# untitled.net
KiCad netlist of a schematic drawn in EAGLE
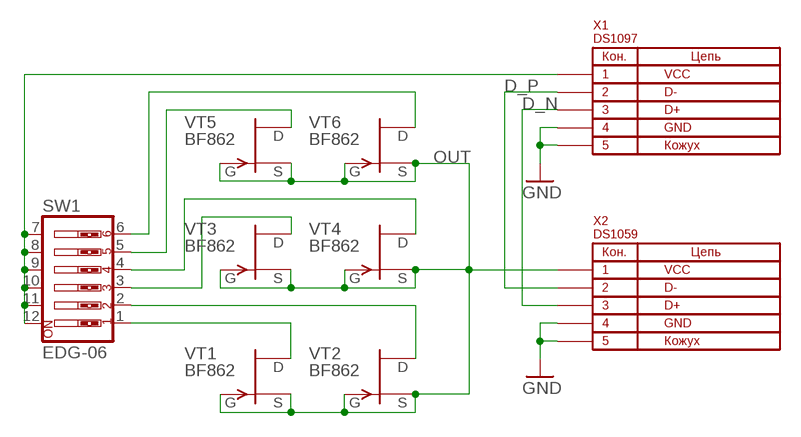
[diagram p0: schematic, sheet 1]

(export (version "E")
  (design (tool "Eeschema 10.0.6"))
  (components
    (comp (ref "SW1")
      (value "EDG-06")
      (footprint "eagle-import:EDG-06")
      (libsource (lib "eagle-import") (part "EDG-06"))
    )
    (comp (ref "VT1")
      (value "BF862")
      (footprint "eagle-import:SOT23")
      (libsource (lib "eagle-import") (part "BF862"))
    )
    (comp (ref "VT2")
      (value "BF862")
      (footprint "eagle-import:SOT23")
      (libsource (lib "eagle-import") (part "BF862"))
    )
    (comp (ref "VT3")
      (value "BF862")
      (footprint "eagle-import:SOT23")
      (libsource (lib "eagle-import") (part "BF862"))
    )
    (comp (ref "VT4")
      (value "BF862")
      (footprint "eagle-import:SOT23")
      (libsource (lib "eagle-import") (part "BF862"))
    )
    (comp (ref "VT5")
      (value "BF862")
      (footprint "eagle-import:SOT23")
      (libsource (lib "eagle-import") (part "BF862"))
    )
    (comp (ref "VT6")
      (value "BF862")
      (footprint "eagle-import:SOT23")
      (libsource (lib "eagle-import") (part "BF862"))
    )
    (comp (ref "X1")
      (value "DS1097")
      (footprint "eagle-import:DS1097")
      (libsource (lib "eagle-import") (part "DS1097"))
    )
    (comp (ref "X2")
      (value "DS1059")
      (footprint "eagle-import:DS1059")
      (libsource (lib "eagle-import") (part "DS1059"))
    )
  )
  (nets
    (net (code "1") (name "/D_N") (class "Default")
      (node (ref "X1") (pin "P$2") (pinfunction "P$3_P$2") (pintype "bidirectional"))
      (node (ref "X2") (pin "P$3") (pinfunction "P$3_P$3") (pintype "bidirectional"))
    )
    (net (code "2") (name "/D_P") (class "Default")
      (node (ref "X1") (pin "P$3") (pinfunction "P$2_P$3") (pintype "bidirectional"))
      (node (ref "X2") (pin "P$2") (pinfunction "P$2_P$2") (pintype "bidirectional"))
    )
    (net (code "3") (name "/OUT") (class "Default")
      (node (ref "VT1") (pin "1") (pinfunction "S_1") (pintype "passive"))
      (node (ref "VT1") (pin "3") (pinfunction "G_3") (pintype "passive"))
      (node (ref "VT2") (pin "1") (pinfunction "S_1") (pintype "passive"))
      (node (ref "VT2") (pin "3") (pinfunction "G_3") (pintype "passive"))
      (node (ref "VT3") (pin "1") (pinfunction "S_1") (pintype "passive"))
      (node (ref "VT3") (pin "3") (pinfunction "G_3") (pintype "passive"))
      (node (ref "VT4") (pin "1") (pinfunction "S_1") (pintype "passive"))
      (node (ref "VT4") (pin "3") (pinfunction "G_3") (pintype "passive"))
      (node (ref "VT5") (pin "1") (pinfunction "S_1") (pintype "passive"))
      (node (ref "VT5") (pin "3") (pinfunction "G_3") (pintype "passive"))
      (node (ref "VT6") (pin "1") (pinfunction "S_1") (pintype "passive"))
      (node (ref "VT6") (pin "3") (pinfunction "G_3") (pintype "passive"))
      (node (ref "X2") (pin "P$1") (pinfunction "P$1_P$1") (pintype "bidirectional"))
    )
    (net (code "4") (name "GND") (class "Default")
      (node (ref "X1") (pin "P$1") (pinfunction "P$4_P$1") (pintype "bidirectional"))
      (node (ref "X1") (pin "P$5") (pinfunction "P$5_P$5") (pintype "bidirectional"))
      (node (ref "X1") (pin "P$6") (pinfunction "P$5_P$6") (pintype "bidirectional"))
      (node (ref "X2") (pin "P$4") (pinfunction "P$4_P$4") (pintype "bidirectional"))
      (node (ref "X2") (pin "P$5") (pinfunction "P$5_P$5") (pintype "bidirectional"))
      (node (ref "X2") (pin "P$6") (pinfunction "P$5_P$6") (pintype "bidirectional"))
    )
    (net (code "5") (name "Net-(VT1-D)") (class "Default")
      (node (ref "SW1") (pin "1") (pinfunction "1_1") (pintype "passive"))
      (node (ref "VT1") (pin "2") (pinfunction "D_2") (pintype "passive"))
    )
    (net (code "6") (name "Net-(VT2-D)") (class "Default")
      (node (ref "SW1") (pin "2") (pinfunction "2_2") (pintype "passive"))
      (node (ref "VT2") (pin "2") (pinfunction "D_2") (pintype "passive"))
    )
    (net (code "7") (name "Net-(VT3-D)") (class "Default")
      (node (ref "SW1") (pin "3") (pinfunction "3_3") (pintype "passive"))
      (node (ref "VT3") (pin "2") (pinfunction "D_2") (pintype "passive"))
    )
    (net (code "8") (name "Net-(VT4-D)") (class "Default")
      (node (ref "SW1") (pin "4") (pinfunction "4_4") (pintype "passive"))
      (node (ref "VT4") (pin "2") (pinfunction "D_2") (pintype "passive"))
    )
    (net (code "9") (name "Net-(VT5-D)") (class "Default")
      (node (ref "SW1") (pin "5") (pinfunction "5_5") (pintype "passive"))
      (node (ref "VT5") (pin "2") (pinfunction "D_2") (pintype "passive"))
    )
    (net (code "10") (name "Net-(VT6-D)") (class "Default")
      (node (ref "SW1") (pin "6") (pinfunction "6_6") (pintype "passive"))
      (node (ref "VT6") (pin "2") (pinfunction "D_2") (pintype "passive"))
    )
    (net (code "11") (name "Net-(X1-P$1)") (class "Default")
      (node (ref "SW1") (pin "10") (pinfunction "10_10") (pintype "passive"))
      (node (ref "SW1") (pin "11") (pinfunction "11_11") (pintype "passive"))
      (node (ref "SW1") (pin "12") (pinfunction "12_12") (pintype "passive"))
      (node (ref "SW1") (pin "7") (pinfunction "7_7") (pintype "passive"))
      (node (ref "SW1") (pin "8") (pinfunction "8_8") (pintype "passive"))
      (node (ref "SW1") (pin "9") (pinfunction "9_9") (pintype "passive"))
      (node (ref "X1") (pin "P$4") (pinfunction "P$1_P$4") (pintype "bidirectional"))
    )
  )
)
